# base_module_e1_0_1.net
KiCad netlist of a schematic drawn in EAGLE
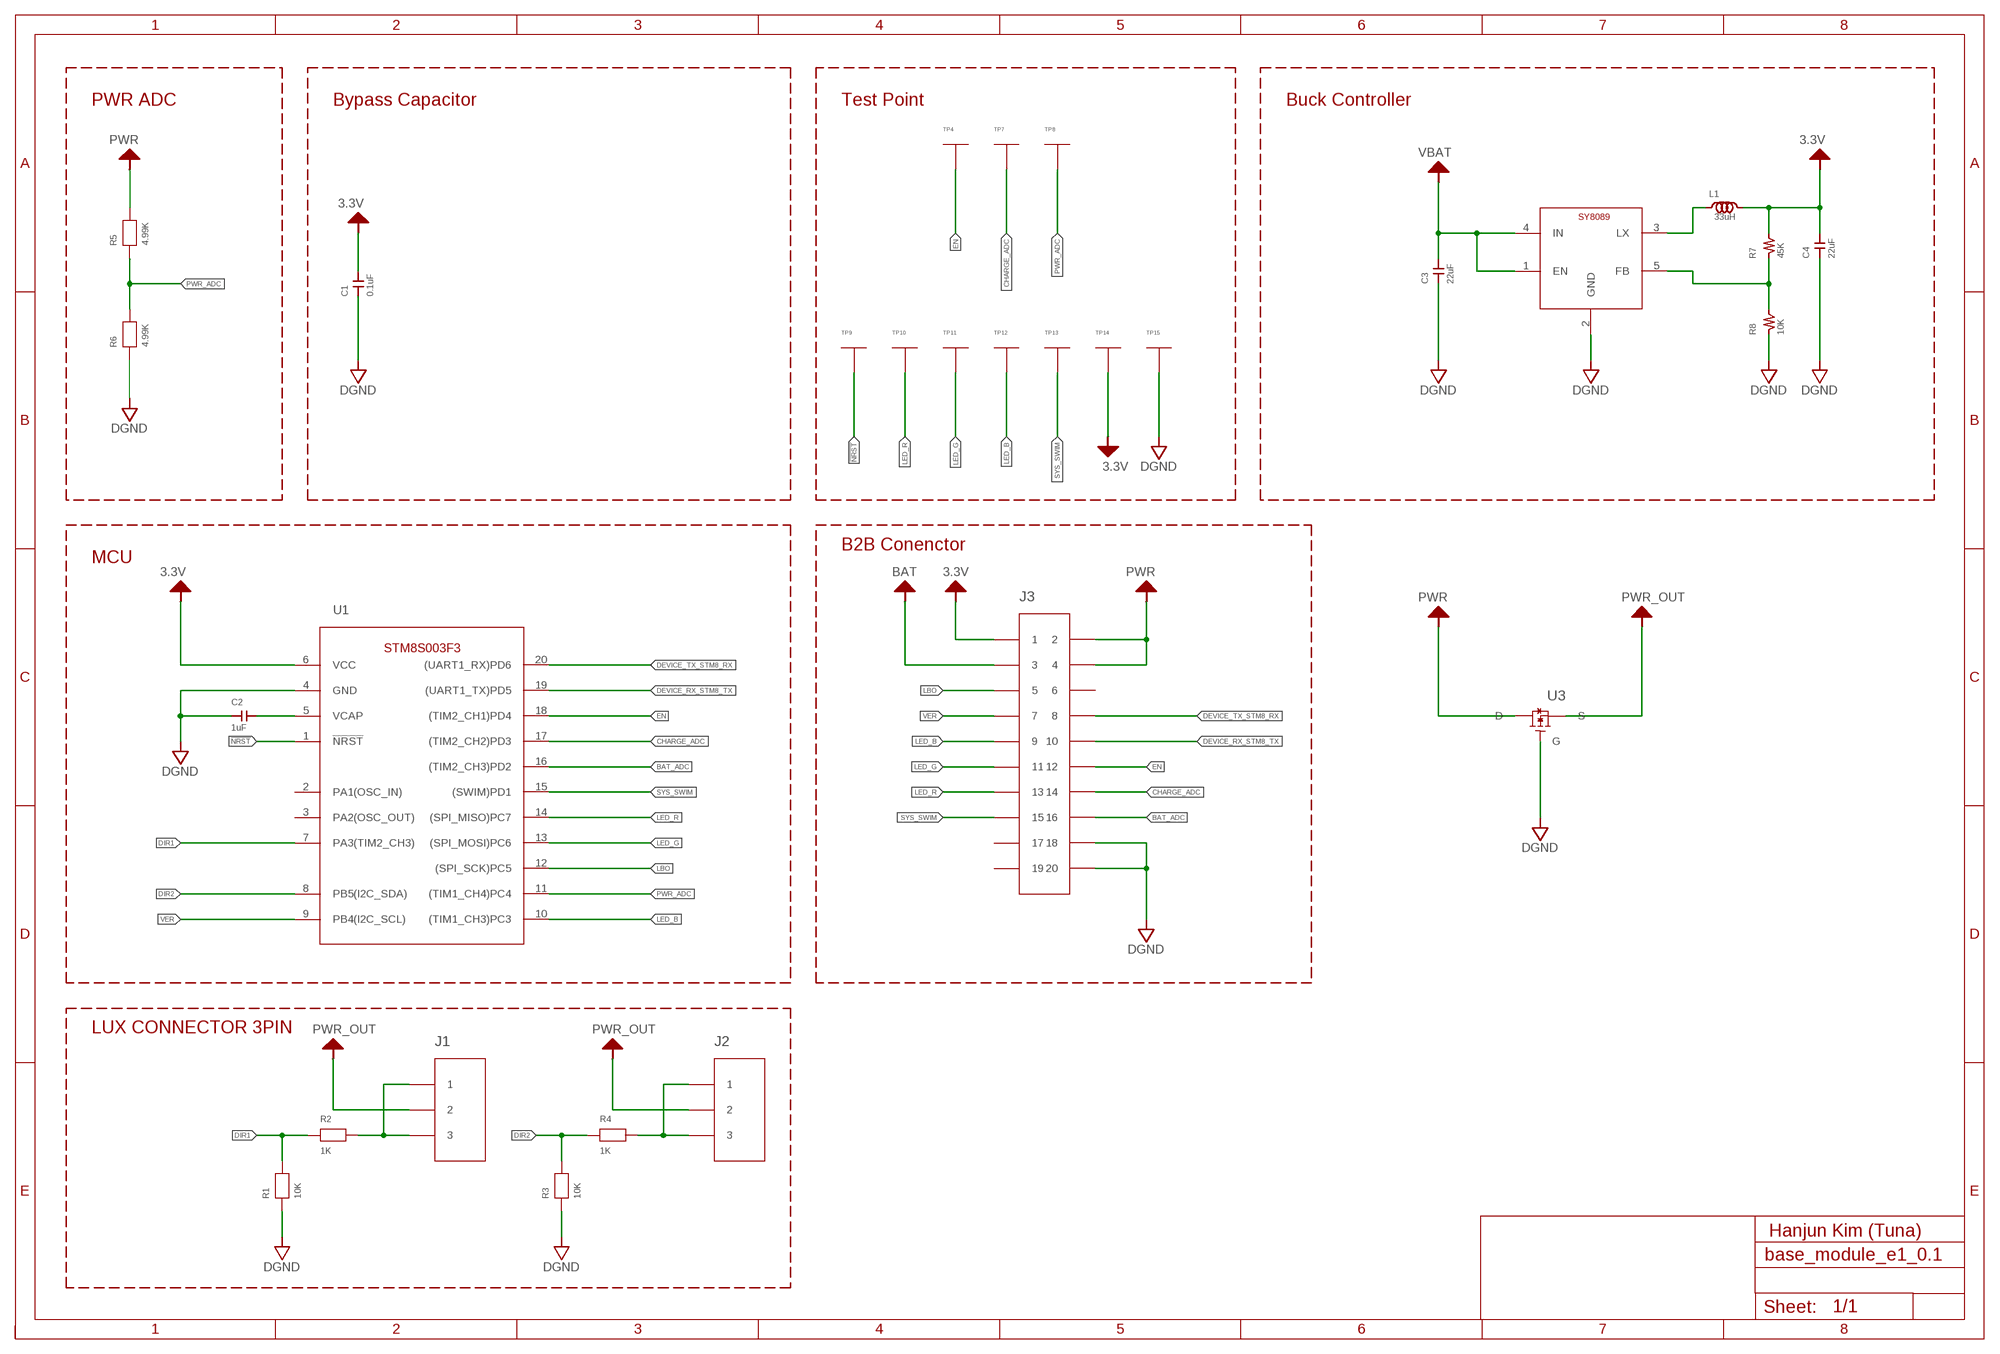
[diagram p0: schematic, sheet 1]

(export (version "E")
  (design (tool "Eeschema 10.0.6"))
  (components
    (comp (ref "C1")
      (value "0.1uF")
      (footprint "eagle-import:1005")
      (libsource (lib "eagle-import") (part "CAPACITOR_CHIP1005"))
    )
    (comp (ref "C2")
      (value "1uF")
      (footprint "eagle-import:1005")
      (libsource (lib "eagle-import") (part "CAPACITOR_CHIP1005"))
    )
    (comp (ref "C3")
      (value "22uF")
      (footprint "eagle-import:1608")
      (libsource (lib "eagle-import") (part "CAPACITOR_CHIP1608"))
    )
    (comp (ref "C4")
      (value "22uF")
      (footprint "eagle-import:1608")
      (libsource (lib "eagle-import") (part "CAPACITOR_CHIP1608"))
    )
    (comp (ref "J1")
      (value "MODI_CONNECTOR_BOTTOM")
      (footprint "eagle-import:3P")
      (libsource (lib "eagle-import") (part "MODI_CONNECTOR_BOTTOM"))
    )
    (comp (ref "J2")
      (value "MODI_CONNECTOR_BOTTOM")
      (footprint "eagle-import:3P")
      (libsource (lib "eagle-import") (part "MODI_CONNECTOR_BOTTOM"))
    )
    (comp (ref "J3")
      (value "AXK720447G")
      (footprint "eagle-import:SOCKET_20P")
      (libsource (lib "eagle-import") (part "AXK720447G"))
    )
    (comp (ref "L1")
      (value "33uH")
      (footprint "eagle-import:2518")
      (libsource (lib "eagle-import") (part "INDUCTOR2518"))
    )
    (comp (ref "P1")
      (value "MODI_BAT_BASE")
      (footprint "eagle-import:BAT_BASE")
      (libsource (lib "eagle-import") (part "MODI_BAT_BASE"))
    )
    (comp (ref "R1")
      (value "10K")
      (footprint "eagle-import:1005")
      (libsource (lib "eagle-import") (part "RESISTOR_CHIP_SMALL1005"))
    )
    (comp (ref "R2")
      (value "1K")
      (footprint "eagle-import:1005")
      (libsource (lib "eagle-import") (part "RESISTOR_CHIP_SMALL1005"))
    )
    (comp (ref "R3")
      (value "10K")
      (footprint "eagle-import:1005")
      (libsource (lib "eagle-import") (part "RESISTOR_CHIP_SMALL1005"))
    )
    (comp (ref "R4")
      (value "1K")
      (footprint "eagle-import:1005")
      (libsource (lib "eagle-import") (part "RESISTOR_CHIP_SMALL1005"))
    )
    (comp (ref "R5")
      (value "4.99K")
      (footprint "eagle-import:1005")
      (libsource (lib "eagle-import") (part "RESISTOR_CHIP_SMALL1005"))
    )
    (comp (ref "R6")
      (value "4.99K")
      (footprint "eagle-import:1005")
      (libsource (lib "eagle-import") (part "RESISTOR_CHIP_SMALL1005"))
    )
    (comp (ref "R7")
      (value "45K")
      (footprint "eagle-import:1005")
      (libsource (lib "eagle-import") (part "RESISTOR_CHIP_1005"))
    )
    (comp (ref "R8")
      (value "10K")
      (footprint "eagle-import:1005")
      (libsource (lib "eagle-import") (part "RESISTOR_CHIP_1005"))
    )
    (comp (ref "TP4")
      (value "TEST_POINT_1.2MM_PAD")
      (footprint "eagle-import:1.2MM_PAD")
      (libsource (lib "eagle-import") (part "TEST_POINT_1.2MM_PAD"))
    )
    (comp (ref "TP7")
      (value "TEST_POINT_1.2MM_PAD")
      (footprint "eagle-import:1.2MM_PAD")
      (libsource (lib "eagle-import") (part "TEST_POINT_1.2MM_PAD"))
    )
    (comp (ref "TP8")
      (value "TEST_POINT_1.2MM_PAD")
      (footprint "eagle-import:1.2MM_PAD")
      (libsource (lib "eagle-import") (part "TEST_POINT_1.2MM_PAD"))
    )
    (comp (ref "TP9")
      (value "TEST_POINT_1.2MM_PAD")
      (footprint "eagle-import:1.2MM_PAD")
      (libsource (lib "eagle-import") (part "TEST_POINT_1.2MM_PAD"))
    )
    (comp (ref "TP10")
      (value "TEST_POINT_1.2MM_PAD")
      (footprint "eagle-import:1.2MM_PAD")
      (libsource (lib "eagle-import") (part "TEST_POINT_1.2MM_PAD"))
    )
    (comp (ref "TP11")
      (value "TEST_POINT_1.2MM_PAD")
      (footprint "eagle-import:1.2MM_PAD")
      (libsource (lib "eagle-import") (part "TEST_POINT_1.2MM_PAD"))
    )
    (comp (ref "TP12")
      (value "TEST_POINT_1.2MM_PAD")
      (footprint "eagle-import:1.2MM_PAD")
      (libsource (lib "eagle-import") (part "TEST_POINT_1.2MM_PAD"))
    )
    (comp (ref "TP13")
      (value "TEST_POINT")
      (footprint "eagle-import:0.7MM_HOLE")
      (libsource (lib "eagle-import") (part "TEST_POINT"))
    )
    (comp (ref "TP14")
      (value "TEST_POINT")
      (footprint "eagle-import:0.7MM_HOLE")
      (libsource (lib "eagle-import") (part "TEST_POINT"))
    )
    (comp (ref "TP15")
      (value "TEST_POINT")
      (footprint "eagle-import:0.7MM_HOLE")
      (libsource (lib "eagle-import") (part "TEST_POINT"))
    )
    (comp (ref "U1")
      (value "STM8S003FXU6")
      (footprint "eagle-import:UFQFPN20")
      (libsource (lib "eagle-import") (part "STM8S003FXU6"))
    )
    (comp (ref "U2")
      (value "SY8089")
      (footprint "eagle-import:SOT-23-5")
      (libsource (lib "eagle-import") (part "SY8089"))
    )
    (comp (ref "U3")
      (value "PMXBXXXXPE")
      (footprint "eagle-import:DFN1010D-3")
      (libsource (lib "eagle-import") (part "PMXBXXXXPE"))
    )
  )
  (nets
    (net (code "1") (name "/~{NRST}") (class "Default")
      (node (ref "TP9") (pin "P1") (pinfunction "P$1_P1") (pintype "bidirectional"))
      (node (ref "U1") (pin "1") (pinfunction "~{NRST}_1") (pintype "bidirectional"))
    )
    (net (code "2") (name "3.3V") (class "Default")
      (node (ref "C1") (pin "P$2") (pinfunction "P$2_P$2") (pintype "passive"))
      (node (ref "C4") (pin "P$2") (pinfunction "P$2_P$2") (pintype "passive"))
      (node (ref "J3") (pin "P1") (pinfunction "1_P1") (pintype "bidirectional"))
      (node (ref "L1") (pin "P$2") (pinfunction "P$2_P$2") (pintype "passive"))
      (node (ref "R7") (pin "P$2") (pinfunction "P$2_P$2") (pintype "passive"))
      (node (ref "TP14") (pin "1") (pinfunction "P$1_1") (pintype "bidirectional"))
      (node (ref "U1") (pin "6") (pinfunction "VCC_6") (pintype "power_in"))
    )
    (net (code "3") (name "BAT") (class "Default")
      (node (ref "C3") (pin "P$2") (pinfunction "P$2_P$2") (pintype "passive"))
      (node (ref "J3") (pin "P3") (pinfunction "3_P3") (pintype "bidirectional"))
      (node (ref "U2") (pin "1") (pinfunction "EN_1") (pintype "bidirectional"))
      (node (ref "U2") (pin "4") (pinfunction "IN_4") (pintype "input"))
    )
    (net (code "4") (name "BAT_ADC") (class "Default")
      (node (ref "J3") (pin "P16") (pinfunction "16_P16") (pintype "bidirectional"))
      (node (ref "U1") (pin "16") (pinfunction "(TIM2_CH3)PD2_16") (pintype "bidirectional"))
    )
    (net (code "5") (name "CHARGE_ADC") (class "Default")
      (node (ref "J3") (pin "P14") (pinfunction "14_P14") (pintype "bidirectional"))
      (node (ref "TP7") (pin "P1") (pinfunction "P$1_P1") (pintype "bidirectional"))
      (node (ref "U1") (pin "17") (pinfunction "(TIM2_CH2)PD3_17") (pintype "bidirectional"))
    )
    (net (code "6") (name "DEVICE_RX_STM8_TX") (class "Default")
      (node (ref "J3") (pin "P10") (pinfunction "10_P10") (pintype "bidirectional"))
      (node (ref "U1") (pin "19") (pinfunction "(UART1_TX)PD5_19") (pintype "bidirectional"))
    )
    (net (code "7") (name "DEVICE_TX_STM8_RX") (class "Default")
      (node (ref "J3") (pin "P8") (pinfunction "8_P8") (pintype "bidirectional"))
      (node (ref "U1") (pin "20") (pinfunction "(UART1_RX)PD6_20") (pintype "bidirectional"))
    )
    (net (code "8") (name "DGND") (class "Default")
      (node (ref "C1") (pin "P$1") (pinfunction "P$1_P$1") (pintype "passive"))
      (node (ref "C2") (pin "P$1") (pinfunction "P$1_P$1") (pintype "passive"))
      (node (ref "C3") (pin "P$1") (pinfunction "P$1_P$1") (pintype "passive"))
      (node (ref "C4") (pin "P$1") (pinfunction "P$1_P$1") (pintype "passive"))
      (node (ref "J3") (pin "P18") (pinfunction "18_P18") (pintype "bidirectional"))
      (node (ref "J3") (pin "P20") (pinfunction "20_P20") (pintype "bidirectional"))
      (node (ref "R1") (pin "P$1") (pinfunction "P$1_P$1") (pintype "bidirectional"))
      (node (ref "R3") (pin "P$1") (pinfunction "P$1_P$1") (pintype "bidirectional"))
      (node (ref "R6") (pin "P$1") (pinfunction "P$1_P$1") (pintype "bidirectional"))
      (node (ref "R8") (pin "P$1") (pinfunction "P$1_P$1") (pintype "passive"))
      (node (ref "TP15") (pin "1") (pinfunction "P$1_1") (pintype "bidirectional"))
      (node (ref "U1") (pin "4") (pinfunction "GND_4") (pintype "power_in"))
      (node (ref "U2") (pin "2") (pinfunction "GND_2") (pintype "power_in"))
      (node (ref "U3") (pin "P1") (pinfunction "G_P1") (pintype "bidirectional"))
    )
    (net (code "9") (name "DIR1") (class "Default")
      (node (ref "R1") (pin "P$2") (pinfunction "P$2_P$2") (pintype "bidirectional"))
      (node (ref "R2") (pin "P$1") (pinfunction "P$1_P$1") (pintype "bidirectional"))
      (node (ref "U1") (pin "7") (pinfunction "PA3(TIM2_CH3)_7") (pintype "bidirectional"))
    )
    (net (code "10") (name "DIR2") (class "Default")
      (node (ref "R3") (pin "P$2") (pinfunction "P$2_P$2") (pintype "bidirectional"))
      (node (ref "R4") (pin "P$1") (pinfunction "P$1_P$1") (pintype "bidirectional"))
      (node (ref "U1") (pin "8") (pinfunction "PB5(I2C_SDA)_8") (pintype "bidirectional"))
    )
    (net (code "11") (name "EN") (class "Default")
      (node (ref "J3") (pin "P12") (pinfunction "12_P12") (pintype "bidirectional"))
      (node (ref "TP4") (pin "P1") (pinfunction "P$1_P1") (pintype "bidirectional"))
      (node (ref "U1") (pin "18") (pinfunction "(TIM2_CH1)PD4_18") (pintype "bidirectional"))
    )
    (net (code "12") (name "LBO") (class "Default")
      (node (ref "J3") (pin "P5") (pinfunction "5_P5") (pintype "bidirectional"))
      (node (ref "U1") (pin "12") (pinfunction "(SPI_SCK)PC5_12") (pintype "bidirectional"))
    )
    (net (code "13") (name "LED_B") (class "Default")
      (node (ref "J3") (pin "P9") (pinfunction "9_P9") (pintype "bidirectional"))
      (node (ref "TP12") (pin "P1") (pinfunction "P$1_P1") (pintype "bidirectional"))
      (node (ref "U1") (pin "10") (pinfunction "(TIM1_CH3)PC3_10") (pintype "bidirectional"))
    )
    (net (code "14") (name "LED_G") (class "Default")
      (node (ref "J3") (pin "P11") (pinfunction "11_P11") (pintype "bidirectional"))
      (node (ref "TP11") (pin "P1") (pinfunction "P$1_P1") (pintype "bidirectional"))
      (node (ref "U1") (pin "13") (pinfunction "(SPI_MOSI)PC6_13") (pintype "bidirectional"))
    )
    (net (code "15") (name "LED_R") (class "Default")
      (node (ref "J3") (pin "P13") (pinfunction "13_P13") (pintype "bidirectional"))
      (node (ref "TP10") (pin "P1") (pinfunction "P$1_P1") (pintype "bidirectional"))
      (node (ref "U1") (pin "14") (pinfunction "(SPI_MISO)PC7_14") (pintype "bidirectional"))
    )
    (net (code "16") (name "Net-(J1-1)") (class "Default")
      (node (ref "J1") (pin "P1") (pinfunction "1_P1") (pintype "bidirectional"))
      (node (ref "J1") (pin "P3") (pinfunction "3_P3") (pintype "bidirectional"))
      (node (ref "R2") (pin "P$2") (pinfunction "P$2_P$2") (pintype "bidirectional"))
    )
    (net (code "17") (name "Net-(J2-1)") (class "Default")
      (node (ref "J2") (pin "P1") (pinfunction "1_P1") (pintype "bidirectional"))
      (node (ref "J2") (pin "P3") (pinfunction "3_P3") (pintype "bidirectional"))
      (node (ref "R4") (pin "P$2") (pinfunction "P$2_P$2") (pintype "bidirectional"))
    )
    (net (code "18") (name "Net-(U1-VCAP)") (class "Default")
      (node (ref "C2") (pin "P$2") (pinfunction "P$2_P$2") (pintype "passive"))
      (node (ref "U1") (pin "5") (pinfunction "VCAP_5") (pintype "power_in"))
    )
    (net (code "19") (name "Net-(U2-FB)") (class "Default")
      (node (ref "R7") (pin "P$1") (pinfunction "P$1_P$1") (pintype "passive"))
      (node (ref "R8") (pin "P$2") (pinfunction "P$2_P$2") (pintype "passive"))
      (node (ref "U2") (pin "5") (pinfunction "FB_5") (pintype "power_in"))
    )
    (net (code "20") (name "Net-(U2-LX)") (class "Default")
      (node (ref "L1") (pin "P$1") (pinfunction "P$1_P$1") (pintype "passive"))
      (node (ref "U2") (pin "3") (pinfunction "LX_3") (pintype "bidirectional"))
    )
    (net (code "21") (name "PWR") (class "Default")
      (node (ref "J3") (pin "P2") (pinfunction "2_P2") (pintype "bidirectional"))
      (node (ref "J3") (pin "P4") (pinfunction "4_P4") (pintype "bidirectional"))
      (node (ref "R5") (pin "P$2") (pinfunction "P$2_P$2") (pintype "bidirectional"))
      (node (ref "U3") (pin "P3") (pinfunction "D_P3") (pintype "bidirectional"))
    )
    (net (code "22") (name "PWR_ADC") (class "Default")
      (node (ref "R5") (pin "P$1") (pinfunction "P$1_P$1") (pintype "bidirectional"))
      (node (ref "R6") (pin "P$2") (pinfunction "P$2_P$2") (pintype "bidirectional"))
      (node (ref "TP8") (pin "P1") (pinfunction "P$1_P1") (pintype "bidirectional"))
      (node (ref "U1") (pin "11") (pinfunction "(TIM1_CH4)PC4_11") (pintype "bidirectional"))
    )
    (net (code "23") (name "PWR_OUT") (class "Default")
      (node (ref "J1") (pin "P2") (pinfunction "2_P2") (pintype "bidirectional"))
      (node (ref "J2") (pin "P2") (pinfunction "2_P2") (pintype "bidirectional"))
      (node (ref "U3") (pin "P2") (pinfunction "S_P2") (pintype "bidirectional"))
    )
    (net (code "24") (name "SYS_SWIM") (class "Default")
      (node (ref "J3") (pin "P15") (pinfunction "15_P15") (pintype "bidirectional"))
      (node (ref "TP13") (pin "1") (pinfunction "P$1_1") (pintype "bidirectional"))
      (node (ref "U1") (pin "15") (pinfunction "(SWIM)PD1_15") (pintype "bidirectional"))
    )
    (net (code "25") (name "VER") (class "Default")
      (node (ref "J3") (pin "P7") (pinfunction "7_P7") (pintype "bidirectional"))
      (node (ref "U1") (pin "9") (pinfunction "PB4(I2C_SCL)_9") (pintype "bidirectional"))
    )
    (net (code "26") (name "unconnected-(J3-6-PadP6)") (class "Default")
      (node (ref "J3") (pin "P6") (pinfunction "6_P6") (pintype "bidirectional"))
    )
    (net (code "27") (name "unconnected-(J3-17-PadP17)") (class "Default")
      (node (ref "J3") (pin "P17") (pinfunction "17_P17") (pintype "bidirectional"))
    )
    (net (code "28") (name "unconnected-(J3-19-PadP19)") (class "Default")
      (node (ref "J3") (pin "P19") (pinfunction "19_P19") (pintype "bidirectional"))
    )
    (net (code "29") (name "unconnected-(U1-PA1(OSC_IN)-Pad2)") (class "Default")
      (node (ref "U1") (pin "2") (pinfunction "PA1(OSC_IN)_2") (pintype "bidirectional"))
    )
    (net (code "30") (name "unconnected-(U1-PA2(OSC_OUT)-Pad3)") (class "Default")
      (node (ref "U1") (pin "3") (pinfunction "PA2(OSC_OUT)_3") (pintype "bidirectional"))
    )
  )
)
